# Buck_Boost_Converter_A.net
KiCad netlist of a schematic drawn in Altium Designer
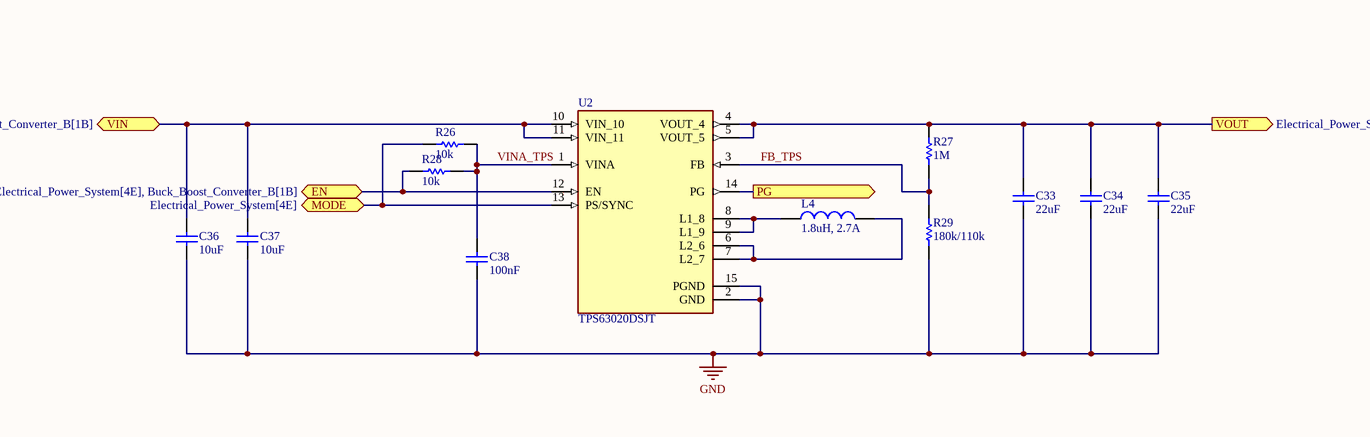
[diagram p0: Buck_Boost_Converter_A.SchDoc, left]
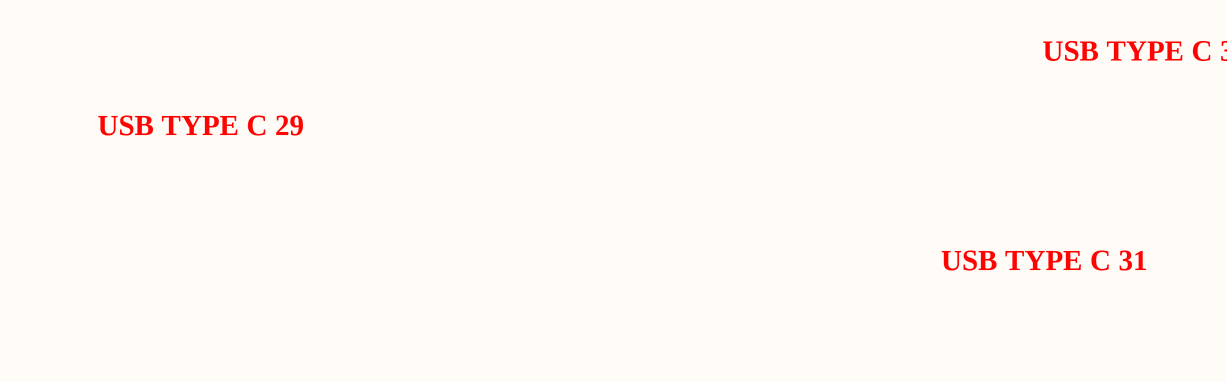
[diagram p1: Buck_Boost_Converter_A.SchDoc, right]

(export (version "E")
  (design (tool "Eeschema 10.0.6"))
  (components
    (comp (ref "C33")
      (value "22uF")
      (footprint "CAP-SM-0603")
      (description "Capacitor")
      (fields (field (name "Comment") "Cap Non-Pol SMD"))
      (libsource (lib "PIF_Library") (part "Cap Non-Pol SMD"))
    )
    (comp (ref "C34")
      (value "22uF")
      (footprint "CAP-SM-0603")
      (description "Capacitor")
      (fields (field (name "Comment") "Cap Non-Pol SMD"))
      (libsource (lib "PIF_Library") (part "Cap Non-Pol SMD"))
    )
    (comp (ref "C35")
      (value "22uF")
      (footprint "CAP-SM-0603")
      (description "Capacitor")
      (fields (field (name "Comment") "Cap Non-Pol SMD"))
      (libsource (lib "PIF_Library") (part "Cap Non-Pol SMD"))
    )
    (comp (ref "C36")
      (value "10uF")
      (footprint "CAP-SM-0603")
      (description "Capacitor")
      (fields (field (name "Comment") "Cap Non-Pol SMD"))
      (libsource (lib "PIF_Library") (part "Cap Non-Pol SMD"))
    )
    (comp (ref "C37")
      (value "10uF")
      (footprint "CAP-SM-0603")
      (description "Capacitor")
      (fields (field (name "Comment") "Cap Non-Pol SMD"))
      (libsource (lib "PIF_Library") (part "Cap Non-Pol SMD"))
    )
    (comp (ref "C38")
      (value "100nF")
      (footprint "CAP-SM-0603")
      (description "Capacitor")
      (fields (field (name "Comment") "Cap Non-Pol SMD"))
      (libsource (lib "PIF_Library") (part "Cap Non-Pol SMD"))
    )
    (comp (ref "L4")
      (value "1.8uH, 2.7A")
      (footprint "WE-PD2A_4532")
      (description "WE-PD2A SMT Power Inductor, size 4532, 1.8uH, 2.7A")
      (fields
        (field (name "MANUFACTURER PART NUMBER") "784773018")
        (field (name "MANUFACTURER") "Wurth Elektronik")
      )
      (libsource (lib "Altium_Coil_Inductor") (part "784773018"))
    )
    (comp (ref "R26")
      (value "10k")
      (footprint "RES-SM-0603")
      (description "Resistor")
      (fields (field (name "Comment") "RESISTOR SMD"))
      (libsource (lib "PIF_Library") (part "RESISTOR SMD"))
    )
    (comp (ref "R27")
      (value "1M")
      (footprint "RES-SM-0603")
      (description "Resistor")
      (fields (field (name "Comment") "RESISTOR SMD"))
      (libsource (lib "PIF_Library") (part "RESISTOR SMD"))
    )
    (comp (ref "R28")
      (value "10k")
      (footprint "RES-SM-0603")
      (description "Resistor")
      (fields (field (name "Comment") "RESISTOR SMD"))
      (libsource (lib "PIF_Library") (part "RESISTOR SMD"))
    )
    (comp (ref "R29")
      (value "180k/110k")
      (footprint "RES-SM-0603")
      (description "Resistor")
      (fields (field (name "Comment") "RESISTOR SMD"))
      (libsource (lib "PIF_Library") (part "RESISTOR SMD"))
    )
    (comp (ref "U2")
      (value "TPS63020DSJT")
      (footprint "IC_TPS63020DSJT")
      (description "High Efficiency Single Inductor Buck-Boost Converter with 4A Switch 14-VSON -40 to 85")
      (fields (field (name "MF") "Texas Instruments"))
      (libsource (lib "EPS_Board_Lib") (part "TPS63020DSJT"))
    )
  )
  (nets
    (net (code "1") (name "/EN") (class "Default")
      (node (ref "R28") (pin "2") (pinfunction "2_2") (pintype "passive"))
      (node (ref "U2") (pin "12") (pinfunction "EN_12") (pintype "input"))
    )
    (net (code "2") (name "/FB_TPS") (class "Default")
      (node (ref "R27") (pin "1") (pinfunction "1_1") (pintype "passive"))
      (node (ref "R29") (pin "2") (pinfunction "2_2") (pintype "passive"))
      (node (ref "U2") (pin "3") (pinfunction "FB_3") (pintype "input"))
    )
    (net (code "3") (name "/MODE") (class "Default")
      (node (ref "R26") (pin "2") (pinfunction "2_2") (pintype "passive"))
      (node (ref "U2") (pin "13") (pinfunction "PS/SYNC_13") (pintype "input"))
    )
    (net (code "4") (name "/PG") (class "Default")
      (node (ref "U2") (pin "14") (pinfunction "PG_14") (pintype "output"))
    )
    (net (code "5") (name "/VIN") (class "Default")
      (node (ref "C36") (pin "2") (pinfunction "2_2") (pintype "passive"))
      (node (ref "C37") (pin "2") (pinfunction "2_2") (pintype "passive"))
      (node (ref "U2") (pin "10") (pinfunction "VIN_10_10") (pintype "input"))
      (node (ref "U2") (pin "11") (pinfunction "VIN_11_11") (pintype "input"))
    )
    (net (code "6") (name "/VINA_TPS") (class "Default")
      (node (ref "C38") (pin "2") (pinfunction "2_2") (pintype "passive"))
      (node (ref "R26") (pin "1") (pinfunction "1_1") (pintype "passive"))
      (node (ref "R28") (pin "1") (pinfunction "1_1") (pintype "passive"))
      (node (ref "U2") (pin "1") (pinfunction "VINA_1") (pintype "input"))
    )
    (net (code "7") (name "/VOUT") (class "Default")
      (node (ref "C33") (pin "2") (pinfunction "2_2") (pintype "passive"))
      (node (ref "C34") (pin "2") (pinfunction "2_2") (pintype "passive"))
      (node (ref "C35") (pin "2") (pinfunction "2_2") (pintype "passive"))
      (node (ref "R27") (pin "2") (pinfunction "2_2") (pintype "passive"))
      (node (ref "U2") (pin "4") (pinfunction "VOUT_4_4") (pintype "output"))
      (node (ref "U2") (pin "5") (pinfunction "VOUT_5_5") (pintype "output"))
    )
    (net (code "8") (name "GND") (class "Default")
      (node (ref "C33") (pin "1") (pinfunction "1_1") (pintype "passive"))
      (node (ref "C34") (pin "1") (pinfunction "1_1") (pintype "passive"))
      (node (ref "C35") (pin "1") (pinfunction "1_1") (pintype "passive"))
      (node (ref "C36") (pin "1") (pinfunction "1_1") (pintype "passive"))
      (node (ref "C37") (pin "1") (pinfunction "1_1") (pintype "passive"))
      (node (ref "C38") (pin "1") (pinfunction "1_1") (pintype "passive"))
      (node (ref "R29") (pin "1") (pinfunction "1_1") (pintype "passive"))
      (node (ref "U2") (pin "15") (pinfunction "PGND_15") (pintype "power_in"))
      (node (ref "U2") (pin "2") (pinfunction "GND_2") (pintype "power_in"))
    )
    (net (code "9") (name "Net-(U2-L1_8)") (class "Default")
      (node (ref "L4") (pin "1") (pinfunction "1_1") (pintype "passive"))
      (node (ref "U2") (pin "8") (pinfunction "L1_8_8") (pintype "passive"))
      (node (ref "U2") (pin "9") (pinfunction "L1_9_9") (pintype "passive"))
    )
    (net (code "10") (name "Net-(U2-L2_6)") (class "Default")
      (node (ref "L4") (pin "2") (pinfunction "2_2") (pintype "passive"))
      (node (ref "U2") (pin "6") (pinfunction "L2_6_6") (pintype "passive"))
      (node (ref "U2") (pin "7") (pinfunction "L2_7_7") (pintype "passive"))
    )
  )
)
